# OpenRing_Power.net
KiCad netlist of a schematic drawn in Altium Designer
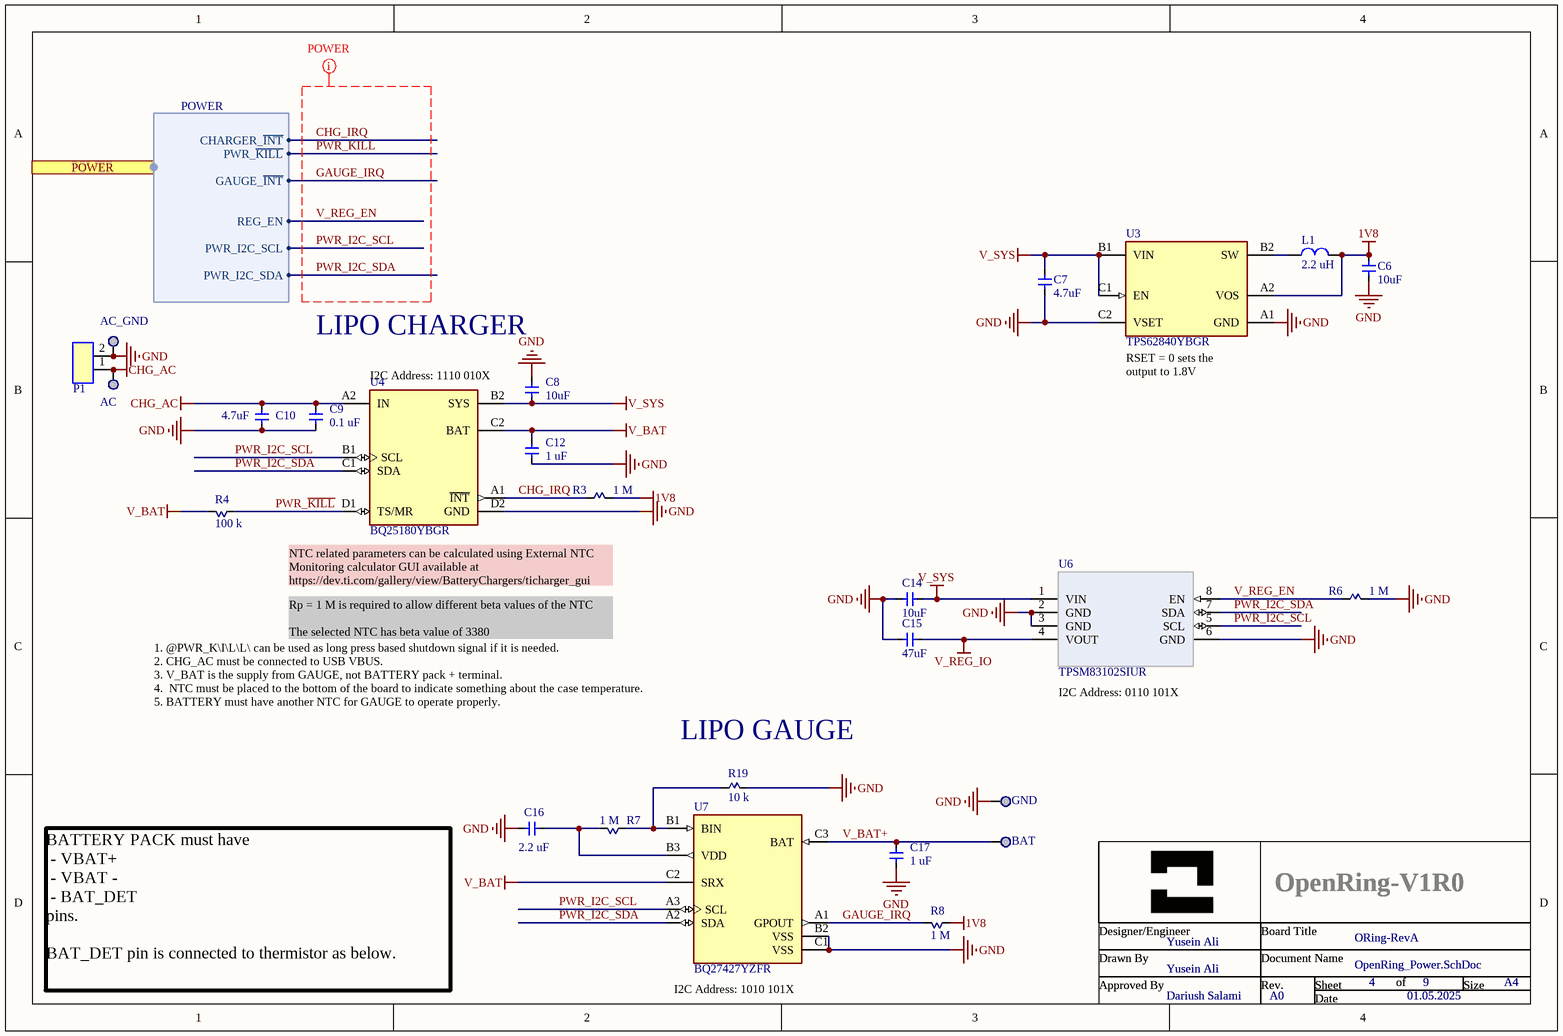
[diagram p0: OpenRing_Power.SchDoc]

(export (version "E")
  (design (tool "Eeschema 10.0.6"))
  (components
    (comp (ref "AC")
      (value "TESTPAD")
      (footprint "TEST_PAD")
      (description "TESTPOINT PIN SMD")
      (libsource (lib "OpenRingComponents") (part "TESTPAD"))
    )
    (comp (ref "AC_GND")
      (value "TESTPAD")
      (footprint "TEST_PAD")
      (description "TESTPOINT PIN SMD")
      (libsource (lib "OpenRingComponents") (part "TESTPAD"))
    )
    (comp (ref "BAT")
      (value "TESTPAD")
      (footprint "TEST_PAD")
      (description "TESTPOINT PIN SMD")
      (libsource (lib "OpenRingComponents") (part "TESTPAD"))
    )
    (comp (ref "C6")
      (value "10uF")
      (footprint "CAPC1005X05N")
      (description "Multilayer Ceramic Capacitor, 10 uF, 10 V, ± 20%, X5R, 0402 [1005 Metric]")
      (fields
        (field (name "MANUFACTURER") "Samsung")
        (field (name "MANUFACTURER PART NUMBER") "CL05A106MP5NUNC")
      )
      (libsource (lib "OpenRingComponents") (part "CL05A106MP5NUNC"))
    )
    (comp (ref "C7")
      (value "4.7uF")
      (footprint "CAPC1005X05N")
      (description "Multilayer Ceramic Capacitor, 4.7 uF, 10 V, ± 20%, X5R, 0402 [1005 Metric]")
      (fields
        (field (name "MANUFACTURER") "Murata")
        (field (name "MANUFACTURER PART NUMBER") "GRM155R61A475MEAAD")
      )
      (libsource (lib "OpenRingComponents") (part "GRM155R61A475MEAAD"))
    )
    (comp (ref "C8")
      (value "10uF")
      (footprint "CAPC1005X05N")
      (description "Multilayer Ceramic Capacitor, 10 uF, 10 V, ± 20%, X5R, 0402 [1005 Metric]")
      (fields
        (field (name "MANUFACTURER") "Samsung")
        (field (name "MANUFACTURER PART NUMBER") "CL05A106MP5NUNC")
      )
      (libsource (lib "OpenRingComponents") (part "CL05A106MP5NUNC"))
    )
    (comp (ref "C9")
      (value "0.1 uF")
      (footprint "CAPC1005X05N")
      (description "CAP CER 0.1UF 16V X5R 0402")
      (fields
        (field (name "MANUFACTURER") "Murata Electronics")
        (field (name "MANUFACTURER PART NUMBER") "GRM155R61C104KA88D")
      )
      (libsource (lib "OpenRingComponents") (part "GRM155R61C104KA88D"))
    )
    (comp (ref "C10")
      (value "4.7uF")
      (footprint "CAPC1005X05N")
      (description "Multilayer Ceramic Capacitor, 4.7 uF, 10 V, ± 20%, X5R, 0402 [1005 Metric]")
      (fields
        (field (name "MANUFACTURER") "Murata")
        (field (name "MANUFACTURER PART NUMBER") "GRM155R61A475MEAAD")
      )
      (libsource (lib "OpenRingComponents") (part "GRM155R61A475MEAAD"))
    )
    (comp (ref "C12")
      (value "1 uF")
      (footprint "CAPC1005X05N")
      (description "CAP CER 1UF 10V X5R 0402")
      (fields
        (field (name "MANUFACTURER") "Murata Electronics North America")
        (field (name "MANUFACTURER PART NUMBER") "GRM155R61A105KE15D")
      )
      (libsource (lib "OpenRingComponents") (part "GRM155R61A105KE15D"))
    )
    (comp (ref "C14")
      (value "10uF")
      (footprint "CAPC1005X05N")
      (description "Multilayer Ceramic Capacitor, 10 uF, 10 V, ± 20%, X5R, 0402 [1005 Metric]")
      (fields
        (field (name "MANUFACTURER") "Samsung")
        (field (name "MANUFACTURER PART NUMBER") "CL05A106MP5NUNC")
      )
      (libsource (lib "OpenRingComponents") (part "CL05A106MP5NUNC"))
    )
    (comp (ref "C15")
      (value "47uF")
      (footprint "CAPC1610X05N")
      (description "CL10 Series 0603 47 uF 6.3 V ±20% Tolerance X5R Multilayer Ceramic Capacitor")
      (fields
        (field (name "MANUFACTURER") "Samsung")
        (field (name "MANUFACTURER PART NUMBER") "CL10A476MQ8QRNC")
      )
      (libsource (lib "OpenRingComponents") (part "CL10A476MQ8QRNC"))
    )
    (comp (ref "C16")
      (value "2.2 uF")
      (footprint "CAPC1005X05N")
      (description "CAP CER 2.2UF 10V X5R 0402")
      (fields
        (field (name "MANUFACTURER") "Murata Electronics North America")
        (field (name "MANUFACTURER PART NUMBER") "GRM155R61A225KE95D")
      )
      (libsource (lib "OpenRingComponents") (part "GRM155R61A225KE95D"))
    )
    (comp (ref "C17")
      (value "1 uF")
      (footprint "CAPC1005X05N")
      (description "CAP CER 1UF 10V X5R 0402")
      (fields
        (field (name "MANUFACTURER") "Murata Electronics North America")
        (field (name "MANUFACTURER PART NUMBER") "GRM155R61A105KE15D")
      )
      (libsource (lib "OpenRingComponents") (part "GRM155R61A105KE15D"))
    )
    (comp (ref "GND")
      (value "TESTPAD")
      (footprint "TEST_PAD")
      (description "TESTPOINT PIN SMD")
      (libsource (lib "OpenRingComponents") (part "TESTPAD"))
    )
    (comp (ref "L1")
      (value "2.2 uH")
      (footprint "FP-DFE201612C-MFG")
      (description "Inductor Power Shielded Wirewound 2.2uH 20% 1MHz Metal 1.8A 0.116Ohm DCR 0806 T/R")
      (fields
        (field (name "MANUFACTURER") "Murata")
        (field (name "MANUFACTURER PART NUMBER") "DFE201612E-2R2M=P2")
      )
      (libsource (lib "OpenRingComponents") (part "DFE201612E-2R2M=P2"))
    )
    (comp (ref "P1")
      (value "RM-1238-B02-41")
      (footprint "RM-1238-B02-41_2")
      (description "RM-1238-B02-41 by www.xtpogopin.com")
      (fields (field (name "MANUFACTURER") "XTPogoPin"))
      (libsource (lib "Connectors") (part "RM-1238-B02-41"))
    )
    (comp (ref "R3")
      (value "1 M")
      (footprint "RESC1005X04N")
      (description "RES SMD 1M OHM 1% 1/10W 0402")
      (fields
        (field (name "MANUFACTURER") "Panasonic Electronic Components")
        (field (name "MANUFACTURER PART NUMBER") "ERJ-2RKF1004X")
      )
      (libsource (lib "OpenRingComponents") (part "ERJ-2RKF1004X"))
    )
    (comp (ref "R4")
      (value "100 k")
      (footprint "RESC1005X04N")
      (description "RES SMD 100K OHM 1% 1/10W 0402")
      (fields
        (field (name "MANUFACTURER") "Panasonic Electronic Components")
        (field (name "MANUFACTURER PART NUMBER") "ERJ-2RKF1003X")
      )
      (libsource (lib "OpenRingComponents") (part "ERJ-2RKF1003X"))
    )
    (comp (ref "R6")
      (value "1 M")
      (footprint "RESC1005X04N")
      (description "RES SMD 1M OHM 1% 1/10W 0402")
      (fields
        (field (name "MANUFACTURER") "Panasonic Electronic Components")
        (field (name "MANUFACTURER PART NUMBER") "ERJ-2RKF1004X")
      )
      (libsource (lib "OpenRingComponents") (part "ERJ-2RKF1004X"))
    )
    (comp (ref "R7")
      (value "1 M")
      (footprint "RESC1005X04N")
      (description "RES SMD 1M OHM 1% 1/10W 0402")
      (fields
        (field (name "MANUFACTURER") "Panasonic Electronic Components")
        (field (name "MANUFACTURER PART NUMBER") "ERJ-2RKF1004X")
      )
      (libsource (lib "OpenRingComponents") (part "ERJ-2RKF1004X"))
    )
    (comp (ref "R8")
      (value "1 M")
      (footprint "RESC1005X04N")
      (description "RES SMD 1M OHM 1% 1/10W 0402")
      (fields
        (field (name "MANUFACTURER") "Panasonic Electronic Components")
        (field (name "MANUFACTURER PART NUMBER") "ERJ-2RKF1004X")
      )
      (libsource (lib "OpenRingComponents") (part "ERJ-2RKF1004X"))
    )
    (comp (ref "R19")
      (value "10 k")
      (footprint "RESC1005X04N")
      (description "RES SMD 10K OHM 1% 1/10W 0402")
      (fields
        (field (name "MANUFACTURER") "Panasonic Electronic Components")
        (field (name "MANUFACTURER PART NUMBER") "ERJ-2RKF1002X")
      )
      (libsource (lib "OpenRingComponents") (part "ERJ-2RKF1002X"))
    )
    (comp (ref "U3")
      (value "TPS62840YBGR")
      (footprint "BGA6C40P2X3_97X147X50")
      (description "Conv DC-DC 1.8V to 6.5V Synchronous Step Down Single-Out 1.8V to 3.3V 0.75A 6-Pin DSBGA T/R")
      (fields (field (name "MANUFACTURER") "Texas Instruments"))
      (libsource (lib "OpenRingComponents") (part "TPS62840YBGR"))
    )
    (comp (ref "U4")
      (value "BQ25180YBGR")
      (footprint "BGA8C40P2X4_104X159X50")
      (description "1-A Li-ion I²C programmable charger with regulated power path in WCSP package 8-DSBGA -40 to 85")
      (fields (field (name "MANUFACTURER") "Texas Instruments"))
      (libsource (lib "OpenRingComponents") (part "BQ25180YBGR"))
    )
    (comp (ref "U6")
      (value "TPSM83102SIUR")
      (footprint "MicroSiP8_SIU-A_TEX-M")
      (fields (field (name "MANUFACTURER") "Texas Instruments"))
      (libsource (lib "OpenRingComponents") (part "TPSM83102SIUR"))
    )
    (comp (ref "U7")
      (value "BQ27427YZFR")
      (footprint "BGA9C50P3X3_158X162X62")
      (fields (field (name "MANUFACTURER") "Texas Instruments"))
      (libsource (lib "OpenRingComponents") (part "BQ27427YZFR"))
    )
  )
  (nets
    (net (code "2") (name "/CHG_IRQ") (class "Default")
      (node (ref "R3") (pin "2") (pinfunction "2_2") (pintype "passive"))
      (node (ref "U4") (pin "A1") (pinfunction "~{INT}_A1") (pintype "output"))
    )
    (net (code "3") (name "/GAUGE_IRQ") (class "Default")
      (node (ref "R8") (pin "2") (pinfunction "2_2") (pintype "passive"))
      (node (ref "U7") (pin "A1") (pinfunction "GPOUT_A1") (pintype "output"))
    )
    (net (code "4") (name "/PWR_I2C_SCL") (class "Default")
      (node (ref "U4") (pin "B1") (pinfunction "SCL_B1") (pintype "bidirectional"))
      (node (ref "U6") (pin "5") (pinfunction "SCL_5") (pintype "bidirectional"))
      (node (ref "U7") (pin "A3") (pinfunction "SCL_A3") (pintype "bidirectional"))
    )
    (net (code "5") (name "/PWR_I2C_SDA") (class "Default")
      (node (ref "U4") (pin "C1") (pinfunction "SDA_C1") (pintype "bidirectional"))
      (node (ref "U6") (pin "7") (pinfunction "SDA_7") (pintype "bidirectional"))
      (node (ref "U7") (pin "A2") (pinfunction "SDA_A2") (pintype "bidirectional"))
    )
    (net (code "6") (name "/PWR_~{KILL}") (class "Default")
      (node (ref "R4") (pin "1") (pinfunction "1_1") (pintype "passive"))
      (node (ref "U4") (pin "D1") (pinfunction "TS/MR_D1") (pintype "bidirectional"))
    )
    (net (code "7") (name "/V_BAT+") (class "Default")
      (node (ref "BAT") (pin "1") (pinfunction "1_1") (pintype "passive"))
      (node (ref "C17") (pin "1") (pinfunction "1_1") (pintype "passive"))
      (node (ref "U7") (pin "C3") (pinfunction "BAT_C3") (pintype "input"))
    )
    (net (code "8") (name "/V_REG_EN") (class "Default")
      (node (ref "R6") (pin "2") (pinfunction "2_2") (pintype "passive"))
      (node (ref "U6") (pin "8") (pinfunction "EN_8") (pintype "input"))
    )
    (net (code "10") (name "1V8") (class "Default")
      (node (ref "C6") (pin "1") (pinfunction "1_1") (pintype "passive"))
      (node (ref "L1") (pin "2") (pinfunction "2_2") (pintype "passive"))
      (node (ref "R3") (pin "1") (pinfunction "1_1") (pintype "passive"))
      (node (ref "R8") (pin "1") (pinfunction "1_1") (pintype "passive"))
      (node (ref "U3") (pin "A2") (pinfunction "VOS_A2") (pintype "power_in"))
    )
    (net (code "11") (name "CHG_AC") (class "Default")
      (node (ref "AC") (pin "1") (pinfunction "1_1") (pintype "passive"))
      (node (ref "C10") (pin "2") (pinfunction "2_2") (pintype "passive"))
      (node (ref "C9") (pin "1") (pinfunction "1_1") (pintype "passive"))
      (node (ref "P1") (pin "1") (pinfunction "1_1") (pintype "passive"))
      (node (ref "U4") (pin "A2") (pinfunction "IN_A2") (pintype "power_in"))
    )
    (net (code "12") (name "GND") (class "Default")
      (node (ref "AC_GND") (pin "1") (pinfunction "1_1") (pintype "passive"))
      (node (ref "C10") (pin "1") (pinfunction "1_1") (pintype "passive"))
      (node (ref "C12") (pin "2") (pinfunction "2_2") (pintype "passive"))
      (node (ref "C14") (pin "1") (pinfunction "1_1") (pintype "passive"))
      (node (ref "C15") (pin "1") (pinfunction "1_1") (pintype "passive"))
      (node (ref "C16") (pin "2") (pinfunction "2_2") (pintype "passive"))
      (node (ref "C17") (pin "2") (pinfunction "2_2") (pintype "passive"))
      (node (ref "C6") (pin "2") (pinfunction "2_2") (pintype "passive"))
      (node (ref "C7") (pin "1") (pinfunction "1_1") (pintype "passive"))
      (node (ref "C8") (pin "2") (pinfunction "2_2") (pintype "passive"))
      (node (ref "C9") (pin "2") (pinfunction "2_2") (pintype "passive"))
      (node (ref "GND") (pin "1") (pinfunction "1_1") (pintype "passive"))
      (node (ref "P1") (pin "2") (pinfunction "2_2") (pintype "passive"))
      (node (ref "R19") (pin "2") (pinfunction "2_2") (pintype "passive"))
      (node (ref "R6") (pin "1") (pinfunction "1_1") (pintype "passive"))
      (node (ref "U3") (pin "A1") (pinfunction "GND_A1") (pintype "power_in"))
      (node (ref "U3") (pin "C2") (pinfunction "VSET_C2") (pintype "power_in"))
      (node (ref "U4") (pin "D2") (pinfunction "GND_D2") (pintype "power_in"))
      (node (ref "U6") (pin "2") (pinfunction "GND_2") (pintype "power_in"))
      (node (ref "U6") (pin "3") (pinfunction "GND_3") (pintype "power_in"))
      (node (ref "U6") (pin "6") (pinfunction "GND_6") (pintype "power_in"))
      (node (ref "U7") (pin "B2") (pinfunction "VSS_B2") (pintype "power_in"))
      (node (ref "U7") (pin "C1") (pinfunction "VSS_C1") (pintype "power_in"))
    )
    (net (code "13") (name "Net-(U3-SW)") (class "Default")
      (node (ref "L1") (pin "1") (pinfunction "1_1") (pintype "passive"))
      (node (ref "U3") (pin "B2") (pinfunction "SW_B2") (pintype "power_in"))
    )
    (net (code "14") (name "Net-(U7-BIN)") (class "Default")
      (node (ref "R19") (pin "1") (pinfunction "1_1") (pintype "passive"))
      (node (ref "R7") (pin "1") (pinfunction "1_1") (pintype "passive"))
      (node (ref "U7") (pin "B1") (pinfunction "BIN_B1") (pintype "input"))
    )
    (net (code "15") (name "Net-(U7-VDD)") (class "Default")
      (node (ref "C16") (pin "1") (pinfunction "1_1") (pintype "passive"))
      (node (ref "R7") (pin "2") (pinfunction "2_2") (pintype "passive"))
      (node (ref "U7") (pin "B3") (pinfunction "VDD_B3") (pintype "output"))
    )
    (net (code "16") (name "V_BAT") (class "Default")
      (node (ref "C12") (pin "1") (pinfunction "1_1") (pintype "passive"))
      (node (ref "R4") (pin "2") (pinfunction "2_2") (pintype "passive"))
      (node (ref "U4") (pin "C2") (pinfunction "BAT_C2") (pintype "power_in"))
      (node (ref "U7") (pin "C2") (pinfunction "SRX_C2") (pintype "power_in"))
    )
    (net (code "17") (name "V_REG_IO") (class "Default")
      (node (ref "C15") (pin "2") (pinfunction "2_2") (pintype "passive"))
      (node (ref "U6") (pin "4") (pinfunction "VOUT_4") (pintype "power_in"))
    )
    (net (code "18") (name "V_SYS") (class "Default")
      (node (ref "C14") (pin "2") (pinfunction "2_2") (pintype "passive"))
      (node (ref "C7") (pin "2") (pinfunction "2_2") (pintype "passive"))
      (node (ref "C8") (pin "1") (pinfunction "1_1") (pintype "passive"))
      (node (ref "U3") (pin "B1") (pinfunction "VIN_B1") (pintype "power_in"))
      (node (ref "U3") (pin "C1") (pinfunction "EN_C1") (pintype "input"))
      (node (ref "U4") (pin "B2") (pinfunction "SYS_B2") (pintype "power_in"))
      (node (ref "U6") (pin "1") (pinfunction "VIN_1") (pintype "power_in"))
    )
  )
)
